# Register.net
KiCad netlist of a schematic drawn in EAGLE
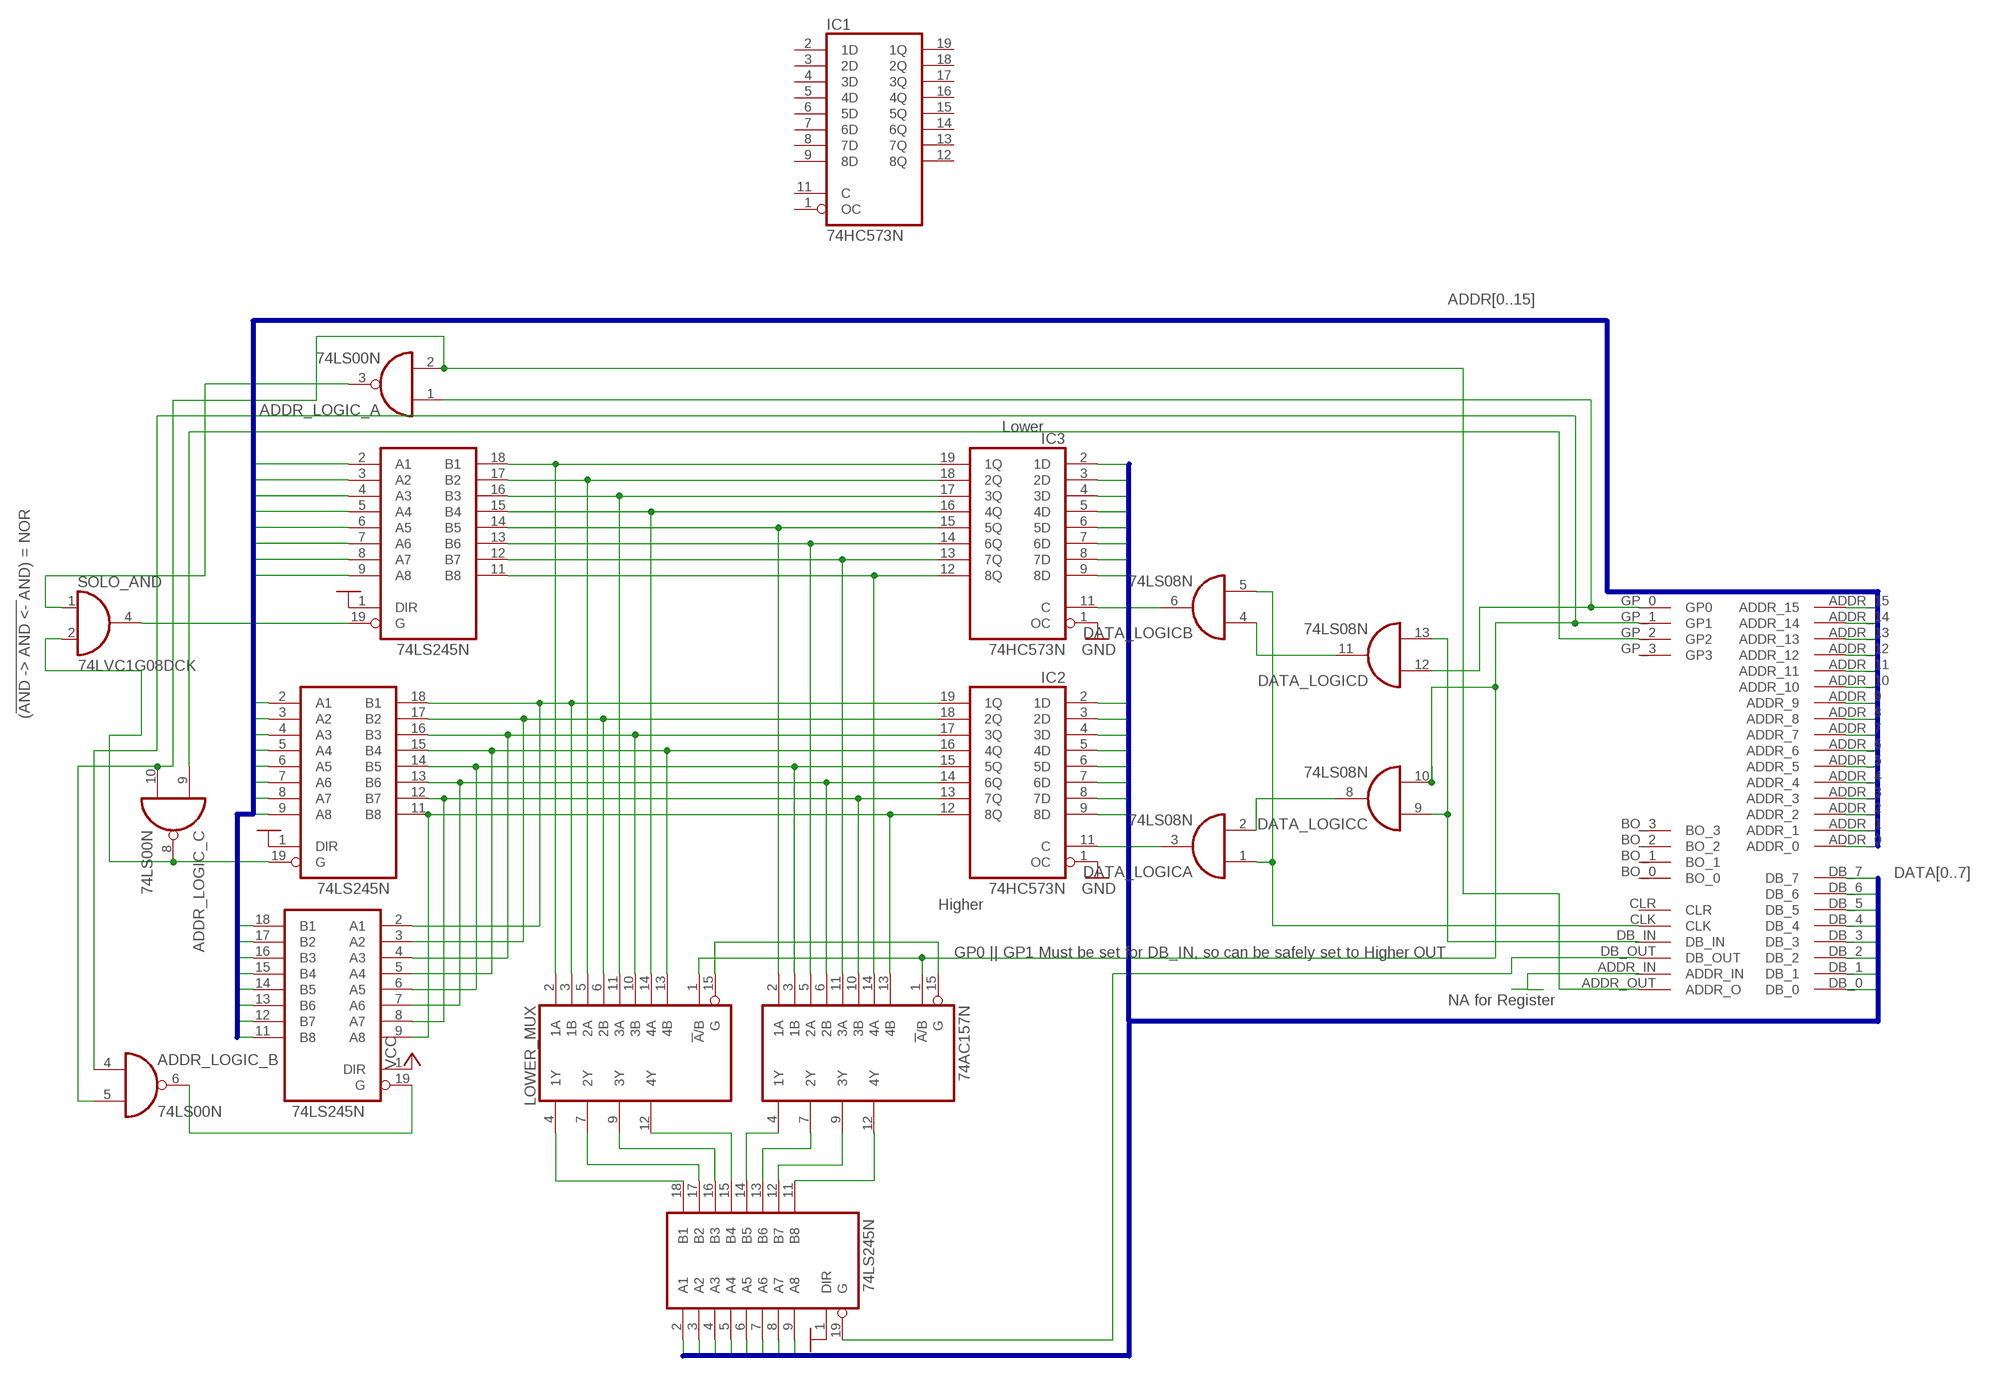
[diagram p0: schematic, sheet 1]

(export (version "E")
  (design (tool "Eeschema 10.0.6"))
  (components
    (comp (ref "ADDR_HIGHER_BUFFER")
      (value "74LS245N")
      (footprint "eagle-import:DIL20")
      (libsource (lib "eagle-import") (part "74245NLS"))
    )
    (comp (ref "ADDR_HIGHER_TO_LOWER")
      (value "74LS245N")
      (footprint "eagle-import:DIL20")
      (libsource (lib "eagle-import") (part "74245NLS"))
    )
    (comp (ref "ADDR_LOGIC_")
      (value "74LS00N")
      (footprint "eagle-import:DIL14")
      (libsource (lib "eagle-import") (part "7400NLS"))
    )
    (comp (ref "ADDR_LOWER_BUFFER")
      (value "74LS245N")
      (footprint "eagle-import:DIL20")
      (libsource (lib "eagle-import") (part "74245NLS"))
    )
    (comp (ref "DATA_LOGIC")
      (value "74LS08N")
      (footprint "eagle-import:DIL14")
      (libsource (lib "eagle-import") (part "7408NLS"))
    )
    (comp (ref "DATA_OUTPUT_BUFFER")
      (value "74LS245N")
      (footprint "eagle-import:DIL20")
      (libsource (lib "eagle-import") (part "74245NLS"))
    )
    (comp (ref "HIGHER_MUX")
      (value "74AC157N")
      (footprint "eagle-import:DIL16")
      (libsource (lib "eagle-import") (part "74157NAC"))
    )
    (comp (ref "IC1")
      (value "74HC573N")
      (footprint "eagle-import:DIL20")
      (libsource (lib "eagle-import") (part "74573NHC"))
    )
    (comp (ref "IC2")
      (value "74HC573N")
      (footprint "eagle-import:DIL20")
      (libsource (lib "eagle-import") (part "74573NHC"))
    )
    (comp (ref "IC3")
      (value "74HC573N")
      (footprint "eagle-import:DIL20")
      (libsource (lib "eagle-import") (part "74573NHC"))
    )
    (comp (ref "LOWER_MUX")
      (value "74AC157N")
      (footprint "eagle-import:DIL16")
      (libsource (lib "eagle-import") (part "74157NAC"))
    )
    (comp (ref "SOLO_AND")
      (value "74LVC1G08DCK")
      (footprint "eagle-import:SC70-5")
      (libsource (lib "eagle-import") (part "741G08DCKLVC"))
    )
    (comp (ref "U$1")
      (value "BACKPLATE_INTERFACEEDGE_FINGER")
      (footprint "eagle-import:BACK_INTERFACE-FOOT")
      (libsource (lib "eagle-import") (part "BACKPLATE_INTERFACEEDGE_FINGER"))
    )
  )
  (nets
    (net (code "1") (name "/ADDR0") (class "Default")
      (node (ref "ADDR_HIGHER_TO_LOWER") (pin "18") (pinfunction "B1_18") (pintype "bidirectional"))
      (node (ref "ADDR_LOWER_BUFFER") (pin "2") (pinfunction "A1_2") (pintype "bidirectional"))
      (node (ref "U$1") (pin "ADDR_0") (pinfunction "ADDR_0_ADDR_0") (pintype "bidirectional"))
    )
    (net (code "2") (name "/ADDR1") (class "Default")
      (node (ref "ADDR_HIGHER_TO_LOWER") (pin "17") (pinfunction "B2_17") (pintype "bidirectional"))
      (node (ref "ADDR_LOWER_BUFFER") (pin "3") (pinfunction "A2_3") (pintype "bidirectional"))
      (node (ref "U$1") (pin "ADDR_1") (pinfunction "ADDR_1_ADDR_1") (pintype "bidirectional"))
    )
    (net (code "3") (name "/ADDR2") (class "Default")
      (node (ref "ADDR_HIGHER_TO_LOWER") (pin "16") (pinfunction "B3_16") (pintype "bidirectional"))
      (node (ref "ADDR_LOWER_BUFFER") (pin "4") (pinfunction "A3_4") (pintype "bidirectional"))
      (node (ref "U$1") (pin "ADDR_2") (pinfunction "ADDR_2_ADDR_2") (pintype "bidirectional"))
    )
    (net (code "4") (name "/ADDR3") (class "Default")
      (node (ref "ADDR_HIGHER_TO_LOWER") (pin "15") (pinfunction "B4_15") (pintype "bidirectional"))
      (node (ref "ADDR_LOWER_BUFFER") (pin "5") (pinfunction "A4_5") (pintype "bidirectional"))
      (node (ref "U$1") (pin "ADDR_3") (pinfunction "ADDR_3_ADDR_3") (pintype "bidirectional"))
    )
    (net (code "5") (name "/ADDR4") (class "Default")
      (node (ref "ADDR_HIGHER_TO_LOWER") (pin "14") (pinfunction "B5_14") (pintype "bidirectional"))
      (node (ref "ADDR_LOWER_BUFFER") (pin "6") (pinfunction "A5_6") (pintype "bidirectional"))
      (node (ref "U$1") (pin "ADDR_4") (pinfunction "ADDR_4_ADDR_4") (pintype "bidirectional"))
    )
    (net (code "6") (name "/ADDR5") (class "Default")
      (node (ref "ADDR_HIGHER_TO_LOWER") (pin "13") (pinfunction "B6_13") (pintype "bidirectional"))
      (node (ref "ADDR_LOWER_BUFFER") (pin "7") (pinfunction "A6_7") (pintype "bidirectional"))
      (node (ref "U$1") (pin "ADDR_5") (pinfunction "ADDR_5_ADDR_5") (pintype "bidirectional"))
    )
    (net (code "7") (name "/ADDR6") (class "Default")
      (node (ref "ADDR_HIGHER_TO_LOWER") (pin "12") (pinfunction "B7_12") (pintype "bidirectional"))
      (node (ref "ADDR_LOWER_BUFFER") (pin "8") (pinfunction "A7_8") (pintype "bidirectional"))
      (node (ref "U$1") (pin "ADDR_6") (pinfunction "ADDR_6_ADDR_6") (pintype "bidirectional"))
    )
    (net (code "8") (name "/ADDR7") (class "Default")
      (node (ref "ADDR_HIGHER_TO_LOWER") (pin "11") (pinfunction "B8_11") (pintype "bidirectional"))
      (node (ref "ADDR_LOWER_BUFFER") (pin "9") (pinfunction "A8_9") (pintype "bidirectional"))
      (node (ref "U$1") (pin "ADDR_7") (pinfunction "ADDR_7_ADDR_7") (pintype "bidirectional"))
    )
    (net (code "9") (name "/ADDR8") (class "Default")
      (node (ref "ADDR_HIGHER_BUFFER") (pin "2") (pinfunction "A1_2") (pintype "bidirectional"))
      (node (ref "U$1") (pin "ADDR_8") (pinfunction "ADDR_8_ADDR_8") (pintype "bidirectional"))
    )
    (net (code "10") (name "/ADDR9") (class "Default")
      (node (ref "ADDR_HIGHER_BUFFER") (pin "3") (pinfunction "A2_3") (pintype "bidirectional"))
      (node (ref "U$1") (pin "ADDR_9") (pinfunction "ADDR_9_ADDR_9") (pintype "bidirectional"))
    )
    (net (code "11") (name "/ADDR10") (class "Default")
      (node (ref "ADDR_HIGHER_BUFFER") (pin "4") (pinfunction "A3_4") (pintype "bidirectional"))
      (node (ref "U$1") (pin "ADDR_10") (pinfunction "ADDR_10_ADDR_10") (pintype "bidirectional"))
    )
    (net (code "12") (name "/ADDR11") (class "Default")
      (node (ref "ADDR_HIGHER_BUFFER") (pin "5") (pinfunction "A4_5") (pintype "bidirectional"))
      (node (ref "U$1") (pin "ADDR_11") (pinfunction "ADDR_11_ADDR_11") (pintype "bidirectional"))
    )
    (net (code "13") (name "/ADDR12") (class "Default")
      (node (ref "ADDR_HIGHER_BUFFER") (pin "6") (pinfunction "A5_6") (pintype "bidirectional"))
      (node (ref "U$1") (pin "ADDR_12") (pinfunction "ADDR_12_ADDR_12") (pintype "bidirectional"))
    )
    (net (code "14") (name "/ADDR13") (class "Default")
      (node (ref "ADDR_HIGHER_BUFFER") (pin "7") (pinfunction "A6_7") (pintype "bidirectional"))
      (node (ref "U$1") (pin "ADDR_13") (pinfunction "ADDR_13_ADDR_13") (pintype "bidirectional"))
    )
    (net (code "15") (name "/ADDR14") (class "Default")
      (node (ref "ADDR_HIGHER_BUFFER") (pin "8") (pinfunction "A7_8") (pintype "bidirectional"))
      (node (ref "U$1") (pin "ADDR_14") (pinfunction "ADDR_14_ADDR_14") (pintype "bidirectional"))
    )
    (net (code "16") (name "/ADDR15") (class "Default")
      (node (ref "ADDR_HIGHER_BUFFER") (pin "9") (pinfunction "A8_9") (pintype "bidirectional"))
      (node (ref "U$1") (pin "ADDR_15") (pinfunction "ADDR_15_ADDR_15") (pintype "bidirectional"))
    )
    (net (code "18") (name "/DATA0") (class "Default")
      (node (ref "DATA_OUTPUT_BUFFER") (pin "2") (pinfunction "A1_2") (pintype "bidirectional"))
      (node (ref "IC2") (pin "2") (pinfunction "1D_2") (pintype "input"))
      (node (ref "IC3") (pin "2") (pinfunction "1D_2") (pintype "input"))
      (node (ref "U$1") (pin "DB_0") (pinfunction "DB_0_DB_0") (pintype "bidirectional"))
    )
    (net (code "19") (name "/DATA1") (class "Default")
      (node (ref "DATA_OUTPUT_BUFFER") (pin "3") (pinfunction "A2_3") (pintype "bidirectional"))
      (node (ref "IC2") (pin "3") (pinfunction "2D_3") (pintype "input"))
      (node (ref "IC3") (pin "3") (pinfunction "2D_3") (pintype "input"))
      (node (ref "U$1") (pin "DB_1") (pinfunction "DB_1_DB_1") (pintype "bidirectional"))
    )
    (net (code "20") (name "/DATA2") (class "Default")
      (node (ref "DATA_OUTPUT_BUFFER") (pin "4") (pinfunction "A3_4") (pintype "bidirectional"))
      (node (ref "IC2") (pin "4") (pinfunction "3D_4") (pintype "input"))
      (node (ref "IC3") (pin "4") (pinfunction "3D_4") (pintype "input"))
      (node (ref "U$1") (pin "DB_2") (pinfunction "DB_2_DB_2") (pintype "bidirectional"))
    )
    (net (code "21") (name "/DATA3") (class "Default")
      (node (ref "DATA_OUTPUT_BUFFER") (pin "5") (pinfunction "A4_5") (pintype "bidirectional"))
      (node (ref "IC2") (pin "5") (pinfunction "4D_5") (pintype "input"))
      (node (ref "IC3") (pin "5") (pinfunction "4D_5") (pintype "input"))
      (node (ref "U$1") (pin "DB_3") (pinfunction "DB_3_DB_3") (pintype "bidirectional"))
    )
    (net (code "22") (name "/DATA4") (class "Default")
      (node (ref "DATA_OUTPUT_BUFFER") (pin "6") (pinfunction "A5_6") (pintype "bidirectional"))
      (node (ref "IC2") (pin "6") (pinfunction "5D_6") (pintype "input"))
      (node (ref "IC3") (pin "6") (pinfunction "5D_6") (pintype "input"))
      (node (ref "U$1") (pin "DB_4") (pinfunction "DB_4_DB_4") (pintype "bidirectional"))
    )
    (net (code "23") (name "/DATA5") (class "Default")
      (node (ref "DATA_OUTPUT_BUFFER") (pin "7") (pinfunction "A6_7") (pintype "bidirectional"))
      (node (ref "IC2") (pin "7") (pinfunction "6D_7") (pintype "input"))
      (node (ref "IC3") (pin "7") (pinfunction "6D_7") (pintype "input"))
      (node (ref "U$1") (pin "DB_5") (pinfunction "DB_5_DB_5") (pintype "bidirectional"))
    )
    (net (code "24") (name "/DATA6") (class "Default")
      (node (ref "DATA_OUTPUT_BUFFER") (pin "8") (pinfunction "A7_8") (pintype "bidirectional"))
      (node (ref "IC2") (pin "8") (pinfunction "7D_8") (pintype "input"))
      (node (ref "IC3") (pin "8") (pinfunction "7D_8") (pintype "input"))
      (node (ref "U$1") (pin "DB_6") (pinfunction "DB_6_DB_6") (pintype "bidirectional"))
    )
    (net (code "25") (name "/DATA7") (class "Default")
      (node (ref "DATA_OUTPUT_BUFFER") (pin "9") (pinfunction "A8_9") (pintype "bidirectional"))
      (node (ref "IC2") (pin "9") (pinfunction "8D_9") (pintype "input"))
      (node (ref "IC3") (pin "9") (pinfunction "8D_9") (pintype "input"))
      (node (ref "U$1") (pin "DB_7") (pinfunction "DB_7_DB_7") (pintype "bidirectional"))
    )
    (net (code "26") (name "GND") (class "Default")
      (node (ref "ADDR_HIGHER_BUFFER") (pin "1") (pinfunction "DIR_1") (pintype "input"))
      (node (ref "ADDR_LOWER_BUFFER") (pin "1") (pinfunction "DIR_1") (pintype "input"))
      (node (ref "DATA_OUTPUT_BUFFER") (pin "1") (pinfunction "DIR_1") (pintype "input"))
      (node (ref "IC2") (pin "1") (pinfunction "OC_1") (pintype "input"))
      (node (ref "IC3") (pin "1") (pinfunction "OC_1") (pintype "input"))
    )
    (net (code "27") (name "Net-(ADDR_HIGHER_BUFFERA-B1)") (class "Default")
      (node (ref "ADDR_HIGHER_BUFFER") (pin "18") (pinfunction "B1_18") (pintype "bidirectional"))
      (node (ref "ADDR_HIGHER_TO_LOWER") (pin "2") (pinfunction "A1_2") (pintype "bidirectional"))
      (node (ref "IC2") (pin "19") (pinfunction "1Q_19") (pintype "tri_state"))
      (node (ref "LOWER_MUX") (pin "3") (pinfunction "1B_3") (pintype "input"))
    )
    (net (code "28") (name "Net-(ADDR_HIGHER_BUFFERA-B2)") (class "Default")
      (node (ref "ADDR_HIGHER_BUFFER") (pin "17") (pinfunction "B2_17") (pintype "bidirectional"))
      (node (ref "ADDR_HIGHER_TO_LOWER") (pin "3") (pinfunction "A2_3") (pintype "bidirectional"))
      (node (ref "IC2") (pin "18") (pinfunction "2Q_18") (pintype "tri_state"))
      (node (ref "LOWER_MUX") (pin "6") (pinfunction "2B_6") (pintype "input"))
    )
    (net (code "29") (name "Net-(ADDR_HIGHER_BUFFERA-B3)") (class "Default")
      (node (ref "ADDR_HIGHER_BUFFER") (pin "16") (pinfunction "B3_16") (pintype "bidirectional"))
      (node (ref "ADDR_HIGHER_TO_LOWER") (pin "4") (pinfunction "A3_4") (pintype "bidirectional"))
      (node (ref "IC2") (pin "17") (pinfunction "3Q_17") (pintype "tri_state"))
      (node (ref "LOWER_MUX") (pin "10") (pinfunction "3B_10") (pintype "input"))
    )
    (net (code "30") (name "Net-(ADDR_HIGHER_BUFFERA-B4)") (class "Default")
      (node (ref "ADDR_HIGHER_BUFFER") (pin "15") (pinfunction "B4_15") (pintype "bidirectional"))
      (node (ref "ADDR_HIGHER_TO_LOWER") (pin "5") (pinfunction "A4_5") (pintype "bidirectional"))
      (node (ref "IC2") (pin "16") (pinfunction "4Q_16") (pintype "tri_state"))
      (node (ref "LOWER_MUX") (pin "13") (pinfunction "4B_13") (pintype "input"))
    )
    (net (code "31") (name "Net-(ADDR_HIGHER_BUFFERA-B5)") (class "Default")
      (node (ref "ADDR_HIGHER_BUFFER") (pin "14") (pinfunction "B5_14") (pintype "bidirectional"))
      (node (ref "ADDR_HIGHER_TO_LOWER") (pin "6") (pinfunction "A5_6") (pintype "bidirectional"))
      (node (ref "HIGHER_MUX") (pin "3") (pinfunction "1B_3") (pintype "input"))
      (node (ref "IC2") (pin "15") (pinfunction "5Q_15") (pintype "tri_state"))
    )
    (net (code "32") (name "Net-(ADDR_HIGHER_BUFFERA-B6)") (class "Default")
      (node (ref "ADDR_HIGHER_BUFFER") (pin "13") (pinfunction "B6_13") (pintype "bidirectional"))
      (node (ref "ADDR_HIGHER_TO_LOWER") (pin "7") (pinfunction "A6_7") (pintype "bidirectional"))
      (node (ref "HIGHER_MUX") (pin "6") (pinfunction "2B_6") (pintype "input"))
      (node (ref "IC2") (pin "14") (pinfunction "6Q_14") (pintype "tri_state"))
    )
    (net (code "33") (name "Net-(ADDR_HIGHER_BUFFERA-B7)") (class "Default")
      (node (ref "ADDR_HIGHER_BUFFER") (pin "12") (pinfunction "B7_12") (pintype "bidirectional"))
      (node (ref "ADDR_HIGHER_TO_LOWER") (pin "8") (pinfunction "A7_8") (pintype "bidirectional"))
      (node (ref "HIGHER_MUX") (pin "10") (pinfunction "3B_10") (pintype "input"))
      (node (ref "IC2") (pin "13") (pinfunction "7Q_13") (pintype "tri_state"))
    )
    (net (code "34") (name "Net-(ADDR_HIGHER_BUFFERA-B8)") (class "Default")
      (node (ref "ADDR_HIGHER_BUFFER") (pin "11") (pinfunction "B8_11") (pintype "bidirectional"))
      (node (ref "ADDR_HIGHER_TO_LOWER") (pin "9") (pinfunction "A8_9") (pintype "bidirectional"))
      (node (ref "HIGHER_MUX") (pin "13") (pinfunction "4B_13") (pintype "input"))
      (node (ref "IC2") (pin "12") (pinfunction "8Q_12") (pintype "tri_state"))
    )
    (net (code "35") (name "Net-(ADDR_HIGHER_BUFFERA-G)") (class "Default")
      (node (ref "ADDR_HIGHER_BUFFER") (pin "19") (pinfunction "G_19") (pintype "input"))
      (node (ref "ADDR_LOGIC_") (pin "8") (pinfunction "O_8") (pintype "output"))
      (node (ref "SOLO_AND") (pin "2") (pinfunction "I1_2") (pintype "input"))
    )
    (net (code "36") (name "Net-(ADDR_HIGHER_TO_LOWERA-G)") (class "Default")
      (node (ref "ADDR_HIGHER_TO_LOWER") (pin "19") (pinfunction "G_19") (pintype "input"))
      (node (ref "ADDR_LOGIC_") (pin "6") (pinfunction "O_6") (pintype "output"))
    )
    (net (code "37") (name "Net-(ADDR_LOGIC_A-I0)") (class "Default")
      (node (ref "ADDR_LOGIC_") (pin "1") (pinfunction "I0_1") (pintype "input"))
      (node (ref "DATA_LOGIC") (pin "12") (pinfunction "I0_12") (pintype "input"))
      (node (ref "U$1") (pin "GP_0") (pinfunction "GP0_GP_0") (pintype "bidirectional"))
    )
    (net (code "38") (name "Net-(ADDR_LOGIC_A-I1)") (class "Default")
      (node (ref "ADDR_LOGIC_") (pin "10") (pinfunction "I1_10") (pintype "input"))
      (node (ref "ADDR_LOGIC_") (pin "2") (pinfunction "I1_2") (pintype "input"))
      (node (ref "ADDR_LOGIC_") (pin "5") (pinfunction "I1_5") (pintype "input"))
      (node (ref "U$1") (pin "ADDR_OUT") (pinfunction "ADDR_O_ADDR_OUT") (pintype "bidirectional"))
    )
    (net (code "39") (name "Net-(ADDR_LOGIC_A-O)") (class "Default")
      (node (ref "ADDR_LOGIC_") (pin "3") (pinfunction "O_3") (pintype "output"))
      (node (ref "SOLO_AND") (pin "1") (pinfunction "I0_1") (pintype "input"))
    )
    (net (code "40") (name "Net-(ADDR_LOGIC_B-I0)") (class "Default")
      (node (ref "ADDR_LOGIC_") (pin "4") (pinfunction "I0_4") (pintype "input"))
      (node (ref "DATA_LOGIC") (pin "10") (pinfunction "I1_10") (pintype "input"))
      (node (ref "HIGHER_MUX") (pin "1") (pinfunction "~{A}/B_1") (pintype "input"))
      (node (ref "LOWER_MUX") (pin "1") (pinfunction "~{A}/B_1") (pintype "input"))
      (node (ref "U$1") (pin "GP_1") (pinfunction "GP1_GP_1") (pintype "bidirectional"))
    )
    (net (code "41") (name "Net-(ADDR_LOGIC_C-I0)") (class "Default")
      (node (ref "ADDR_LOGIC_") (pin "9") (pinfunction "I0_9") (pintype "input"))
      (node (ref "U$1") (pin "GP_2") (pinfunction "GP2_GP_2") (pintype "bidirectional"))
    )
    (net (code "42") (name "Net-(ADDR_LOWER_BUFFERA-B1)") (class "Default")
      (node (ref "ADDR_LOWER_BUFFER") (pin "18") (pinfunction "B1_18") (pintype "bidirectional"))
      (node (ref "IC3") (pin "19") (pinfunction "1Q_19") (pintype "tri_state"))
      (node (ref "LOWER_MUX") (pin "2") (pinfunction "1A_2") (pintype "input"))
    )
    (net (code "43") (name "Net-(ADDR_LOWER_BUFFERA-B2)") (class "Default")
      (node (ref "ADDR_LOWER_BUFFER") (pin "17") (pinfunction "B2_17") (pintype "bidirectional"))
      (node (ref "IC3") (pin "18") (pinfunction "2Q_18") (pintype "tri_state"))
      (node (ref "LOWER_MUX") (pin "5") (pinfunction "2A_5") (pintype "input"))
    )
    (net (code "44") (name "Net-(ADDR_LOWER_BUFFERA-B3)") (class "Default")
      (node (ref "ADDR_LOWER_BUFFER") (pin "16") (pinfunction "B3_16") (pintype "bidirectional"))
      (node (ref "IC3") (pin "17") (pinfunction "3Q_17") (pintype "tri_state"))
      (node (ref "LOWER_MUX") (pin "11") (pinfunction "3A_11") (pintype "input"))
    )
    (net (code "45") (name "Net-(ADDR_LOWER_BUFFERA-B4)") (class "Default")
      (node (ref "ADDR_LOWER_BUFFER") (pin "15") (pinfunction "B4_15") (pintype "bidirectional"))
      (node (ref "IC3") (pin "16") (pinfunction "4Q_16") (pintype "tri_state"))
      (node (ref "LOWER_MUX") (pin "14") (pinfunction "4A_14") (pintype "input"))
    )
    (net (code "46") (name "Net-(ADDR_LOWER_BUFFERA-B5)") (class "Default")
      (node (ref "ADDR_LOWER_BUFFER") (pin "14") (pinfunction "B5_14") (pintype "bidirectional"))
      (node (ref "HIGHER_MUX") (pin "2") (pinfunction "1A_2") (pintype "input"))
      (node (ref "IC3") (pin "15") (pinfunction "5Q_15") (pintype "tri_state"))
    )
    (net (code "47") (name "Net-(ADDR_LOWER_BUFFERA-B6)") (class "Default")
      (node (ref "ADDR_LOWER_BUFFER") (pin "13") (pinfunction "B6_13") (pintype "bidirectional"))
      (node (ref "HIGHER_MUX") (pin "5") (pinfunction "2A_5") (pintype "input"))
      (node (ref "IC3") (pin "14") (pinfunction "6Q_14") (pintype "tri_state"))
    )
    (net (code "48") (name "Net-(ADDR_LOWER_BUFFERA-B7)") (class "Default")
      (node (ref "ADDR_LOWER_BUFFER") (pin "12") (pinfunction "B7_12") (pintype "bidirectional"))
      (node (ref "HIGHER_MUX") (pin "11") (pinfunction "3A_11") (pintype "input"))
      (node (ref "IC3") (pin "13") (pinfunction "7Q_13") (pintype "tri_state"))
    )
    (net (code "49") (name "Net-(ADDR_LOWER_BUFFERA-B8)") (class "Default")
      (node (ref "ADDR_LOWER_BUFFER") (pin "11") (pinfunction "B8_11") (pintype "bidirectional"))
      (node (ref "HIGHER_MUX") (pin "14") (pinfunction "4A_14") (pintype "input"))
      (node (ref "IC3") (pin "12") (pinfunction "8Q_12") (pintype "tri_state"))
    )
    (net (code "50") (name "Net-(ADDR_LOWER_BUFFERA-G)") (class "Default")
      (node (ref "ADDR_LOWER_BUFFER") (pin "19") (pinfunction "G_19") (pintype "input"))
      (node (ref "SOLO_AND") (pin "4") (pinfunction "O_4") (pintype "output"))
    )
    (net (code "51") (name "Net-(DATA_LOGICA-I0)") (class "Default")
      (node (ref "DATA_LOGIC") (pin "1") (pinfunction "I0_1") (pintype "input"))
      (node (ref "DATA_LOGIC") (pin "5") (pinfunction "I1_5") (pintype "input"))
      (node (ref "U$1") (pin "CLK") (pinfunction "CLK_CLK") (pintype "bidirectional"))
    )
    (net (code "52") (name "Net-(DATA_LOGICA-I1)") (class "Default")
      (node (ref "DATA_LOGIC") (pin "2") (pinfunction "I1_2") (pintype "input"))
      (node (ref "DATA_LOGIC") (pin "8") (pinfunction "O_8") (pintype "output"))
    )
    (net (code "53") (name "Net-(DATA_LOGICA-O)") (class "Default")
      (node (ref "DATA_LOGIC") (pin "3") (pinfunction "O_3") (pintype "output"))
      (node (ref "IC2") (pin "11") (pinfunction "C_11") (pintype "input"))
    )
    (net (code "54") (name "Net-(DATA_LOGICB-I0)") (class "Default")
      (node (ref "DATA_LOGIC") (pin "11") (pinfunction "O_11") (pintype "output"))
      (node (ref "DATA_LOGIC") (pin "4") (pinfunction "I0_4") (pintype "input"))
    )
    (net (code "55") (name "Net-(DATA_LOGICB-O)") (class "Default")
      (node (ref "DATA_LOGIC") (pin "6") (pinfunction "O_6") (pintype "output"))
      (node (ref "IC3") (pin "11") (pinfunction "C_11") (pintype "input"))
    )
    (net (code "56") (name "Net-(DATA_LOGICC-I0)") (class "Default")
      (node (ref "DATA_LOGIC") (pin "13") (pinfunction "I1_13") (pintype "input"))
      (node (ref "DATA_LOGIC") (pin "9") (pinfunction "I0_9") (pintype "input"))
      (node (ref "U$1") (pin "DB_IN") (pinfunction "DB_IN_DB_IN") (pintype "bidirectional"))
    )
    (net (code "57") (name "Net-(DATA_OUTPUT_BUFFERA-B1)") (class "Default")
      (node (ref "DATA_OUTPUT_BUFFER") (pin "18") (pinfunction "B1_18") (pintype "bidirectional"))
      (node (ref "LOWER_MUX") (pin "4") (pinfunction "1Y_4") (pintype "output"))
    )
    (net (code "58") (name "Net-(DATA_OUTPUT_BUFFERA-B2)") (class "Default")
      (node (ref "DATA_OUTPUT_BUFFER") (pin "17") (pinfunction "B2_17") (pintype "bidirectional"))
      (node (ref "LOWER_MUX") (pin "7") (pinfunction "2Y_7") (pintype "output"))
    )
    (net (code "59") (name "Net-(DATA_OUTPUT_BUFFERA-B3)") (class "Default")
      (node (ref "DATA_OUTPUT_BUFFER") (pin "16") (pinfunction "B3_16") (pintype "bidirectional"))
      (node (ref "LOWER_MUX") (pin "9") (pinfunction "3Y_9") (pintype "output"))
    )
    (net (code "60") (name "Net-(DATA_OUTPUT_BUFFERA-B4)") (class "Default")
      (node (ref "DATA_OUTPUT_BUFFER") (pin "15") (pinfunction "B4_15") (pintype "bidirectional"))
      (node (ref "LOWER_MUX") (pin "12") (pinfunction "4Y_12") (pintype "output"))
    )
    (net (code "61") (name "Net-(DATA_OUTPUT_BUFFERA-B5)") (class "Default")
      (node (ref "DATA_OUTPUT_BUFFER") (pin "14") (pinfunction "B5_14") (pintype "bidirectional"))
      (node (ref "HIGHER_MUX") (pin "4") (pinfunction "1Y_4") (pintype "output"))
    )
    (net (code "62") (name "Net-(DATA_OUTPUT_BUFFERA-B6)") (class "Default")
      (node (ref "DATA_OUTPUT_BUFFER") (pin "13") (pinfunction "B6_13") (pintype "bidirectional"))
      (node (ref "HIGHER_MUX") (pin "7") (pinfunction "2Y_7") (pintype "output"))
    )
    (net (code "63") (name "Net-(DATA_OUTPUT_BUFFERA-B7)") (class "Default")
      (node (ref "DATA_OUTPUT_BUFFER") (pin "12") (pinfunction "B7_12") (pintype "bidirectional"))
      (node (ref "HIGHER_MUX") (pin "9") (pinfunction "3Y_9") (pintype "output"))
    )
    (net (code "64") (name "Net-(DATA_OUTPUT_BUFFERA-B8)") (class "Default")
      (node (ref "DATA_OUTPUT_BUFFER") (pin "11") (pinfunction "B8_11") (pintype "bidirectional"))
      (node (ref "HIGHER_MUX") (pin "12") (pinfunction "4Y_12") (pintype "output"))
    )
    (net (code "65") (name "Net-(DATA_OUTPUT_BUFFERA-G)") (class "Default")
      (node (ref "DATA_OUTPUT_BUFFER") (pin "19") (pinfunction "G_19") (pintype "input"))
      (node (ref "U$1") (pin "DB_OUT") (pinfunction "DB_OUT_DB_OUT") (pintype "bidirectional"))
    )
    (net (code "66") (name "Net-(HIGHER_MUXA-G)") (class "Default")
      (node (ref "HIGHER_MUX") (pin "15") (pinfunction "G_15") (pintype "input"))
      (node (ref "LOWER_MUX") (pin "15") (pinfunction "G_15") (pintype "input"))
    )
    (net (code "67") (name "VCC") (class "Default")
      (node (ref "ADDR_HIGHER_TO_LOWER") (pin "1") (pinfunction "DIR_1") (pintype "input"))
    )
    (net (code "68") (name "unconnected-(IC1A-1D-Pad2)") (class "Default")
      (node (ref "IC1") (pin "2") (pinfunction "1D_2") (pintype "input"))
    )
    (net (code "69") (name "unconnected-(IC1A-1Q-Pad19)") (class "Default")
      (node (ref "IC1") (pin "19") (pinfunction "1Q_19") (pintype "tri_state"))
    )
    (net (code "70") (name "unconnected-(IC1A-2D-Pad3)") (class "Default")
      (node (ref "IC1") (pin "3") (pinfunction "2D_3") (pintype "input"))
    )
    (net (code "71") (name "unconnected-(IC1A-2Q-Pad18)") (class "Default")
      (node (ref "IC1") (pin "18") (pinfunction "2Q_18") (pintype "tri_state"))
    )
    (net (code "72") (name "unconnected-(IC1A-3D-Pad4)") (class "Default")
      (node (ref "IC1") (pin "4") (pinfunction "3D_4") (pintype "input"))
    )
    (net (code "73") (name "unconnected-(IC1A-3Q-Pad17)") (class "Default")
      (node (ref "IC1") (pin "17") (pinfunction "3Q_17") (pintype "tri_state"))
    )
    (net (code "74") (name "unconnected-(IC1A-4D-Pad5)") (class "Default")
      (node (ref "IC1") (pin "5") (pinfunction "4D_5") (pintype "input"))
    )
    (net (code "75") (name "unconnected-(IC1A-4Q-Pad16)") (class "Default")
      (node (ref "IC1") (pin "16") (pinfunction "4Q_16") (pintype "tri_state"))
    )
    (net (code "76") (name "unconnected-(IC1A-5D-Pad6)") (class "Default")
      (node (ref "IC1") (pin "6") (pinfunction "5D_6") (pintype "input"))
    )
    (net (code "77") (name "unconnected-(IC1A-5Q-Pad15)") (class "Default")
      (node (ref "IC1") (pin "15") (pinfunction "5Q_15") (pintype "tri_state"))
    )
    (net (code "78") (name "unconnected-(IC1A-6D-Pad7)") (class "Default")
      (node (ref "IC1") (pin "7") (pinfunction "6D_7") (pintype "input"))
    )
    (net (code "79") (name "unconnected-(IC1A-6Q-Pad14)") (class "Default")
      (node (ref "IC1") (pin "14") (pinfunction "6Q_14") (pintype "tri_state"))
    )
    (net (code "80") (name "unconnected-(IC1A-7D-Pad8)") (class "Default")
      (node (ref "IC1") (pin "8") (pinfunction "7D_8") (pintype "input"))
    )
    (net (code "81") (name "unconnected-(IC1A-7Q-Pad13)") (class "Default")
      (node (ref "IC1") (pin "13") (pinfunction "7Q_13") (pintype "tri_state"))
    )
    (net (code "82") (name "unconnected-(IC1A-8D-Pad9)") (class "Default")
      (node (ref "IC1") (pin "9") (pinfunction "8D_9") (pintype "input"))
    )
    (net (code "83") (name "unconnected-(IC1A-8Q-Pad12)") (class "Default")
      (node (ref "IC1") (pin "12") (pinfunction "8Q_12") (pintype "tri_state"))
    )
    (net (code "84") (name "unconnected-(IC1A-C-Pad11)") (class "Default")
      (node (ref "IC1") (pin "11") (pinfunction "C_11") (pintype "input"))
    )
    (net (code "85") (name "unconnected-(IC1A-OC-Pad1)") (class "Default")
      (node (ref "IC1") (pin "1") (pinfunction "OC_1") (pintype "input"))
    )
    (net (code "86") (name "unconnected-(U$1-PadADDR_IN)") (class "Default")
      (node (ref "U$1") (pin "ADDR_IN") (pinfunction "ADDR_IN_ADDR_IN") (pintype "bidirectional"))
    )
    (net (code "87") (name "unconnected-(U$1-PadBO_0)") (class "Default")
      (node (ref "U$1") (pin "BO_0") (pinfunction "BO_0_BO_0") (pintype "bidirectional"))
    )
    (net (code "88") (name "unconnected-(U$1-PadBO_1)") (class "Default")
      (node (ref "U$1") (pin "BO_1") (pinfunction "BO_1_BO_1") (pintype "bidirectional"))
    )
    (net (code "89") (name "unconnected-(U$1-PadBO_2)") (class "Default")
      (node (ref "U$1") (pin "BO_2") (pinfunction "BO_2_BO_2") (pintype "bidirectional"))
    )
    (net (code "90") (name "unconnected-(U$1-PadBO_3)") (class "Default")
      (node (ref "U$1") (pin "BO_3") (pinfunction "BO_3_BO_3") (pintype "bidirectional"))
    )
    (net (code "91") (name "unconnected-(U$1-PadCLR)") (class "Default")
      (node (ref "U$1") (pin "CLR") (pinfunction "CLR_CLR") (pintype "bidirectional"))
    )
    (net (code "92") (name "unconnected-(U$1A-GP3-PadGP_3)") (class "Default")
      (node (ref "U$1") (pin "GP_3") (pinfunction "GP3_GP_3") (pintype "bidirectional"))
    )
  )
)
